# SerialPort.net
KiCad netlist of a schematic drawn in Altium Designer
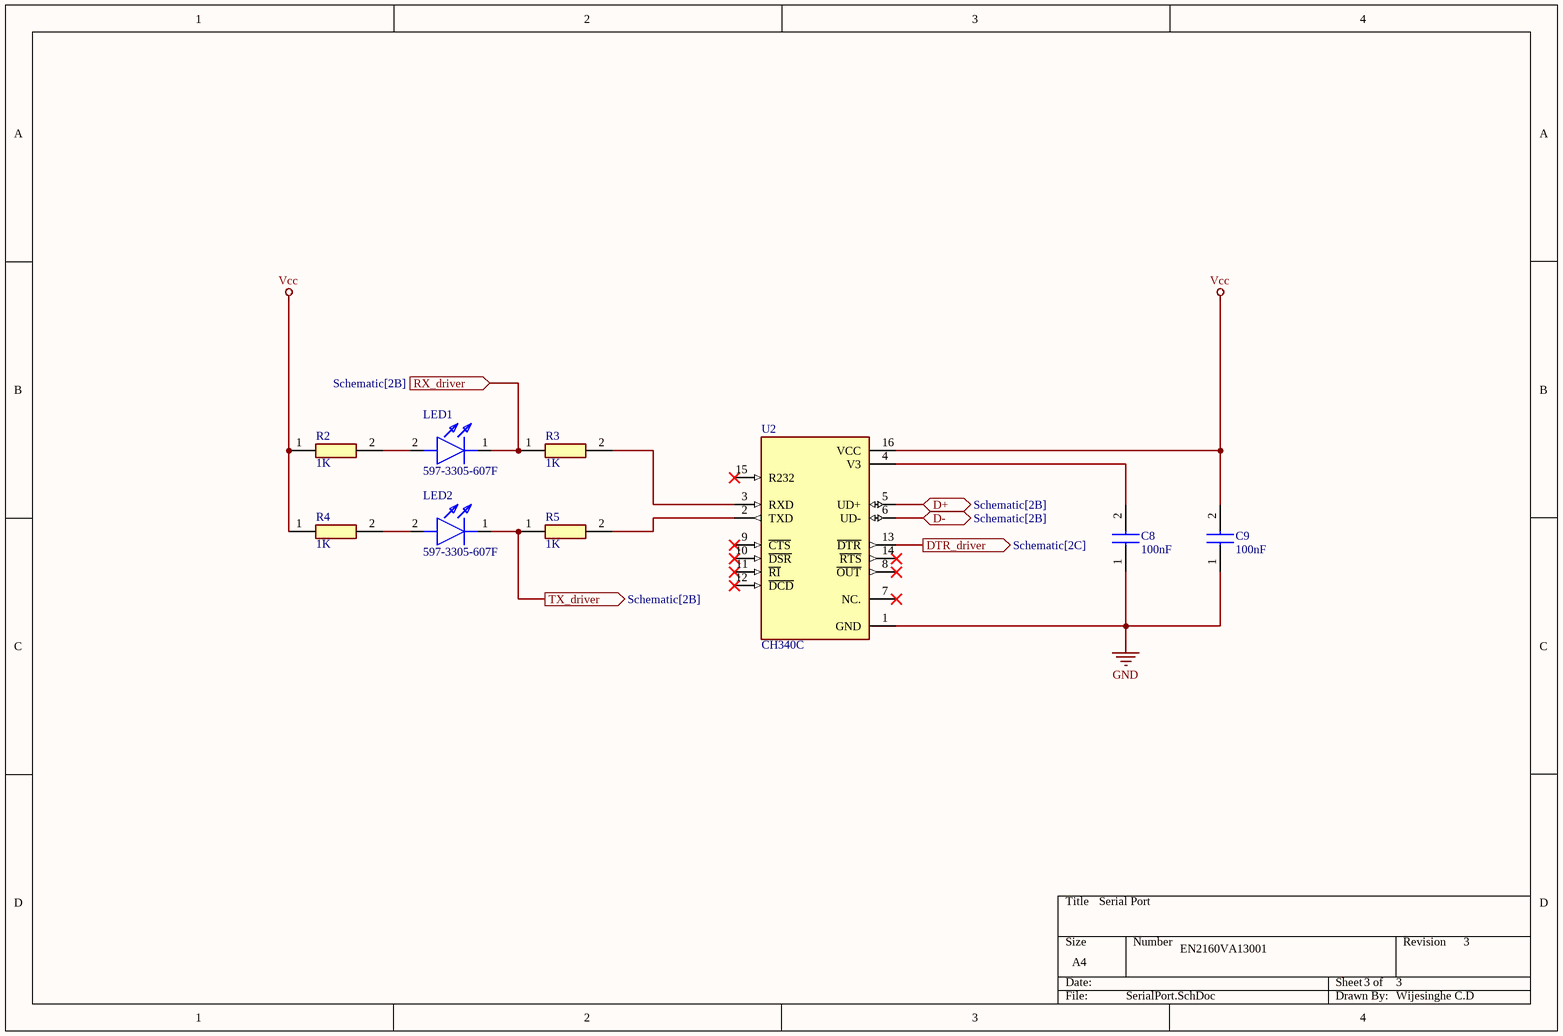
[diagram p0: SerialPort.SchDoc]

(export (version "E")
  (design (tool "Eeschema 10.0.6"))
  (components
    (comp (ref "C8")
      (value "100nF")
      (footprint "SamacSys:CAPC2013X137N")
      (description "Capacitor")
      (fields
        (field (name "MANUFACTURER_PART_NUMBER") "0805B104K500NT")
        (field (name "MOUSER PART NUMBER") "767-0805B104K500NT")
      )
      (libsource (lib "*") (part "0805B104K500NT"))
    )
    (comp (ref "C9")
      (value "100nF")
      (footprint "SamacSys:CAPC2013X137N")
      (description "Capacitor")
      (fields
        (field (name "MANUFACTURER_PART_NUMBER") "0805B104K500NT")
        (field (name "MOUSER PART NUMBER") "767-0805B104K500NT")
      )
      (libsource (lib "*") (part "0805B104K500NT"))
    )
    (comp (ref "LED1")
      (value "597-3305-607F")
      (footprint "SamacSys:LEDC2012X70N")
      (description "LED")
      (fields (field (name "MOUSER PART NUMBER") "645-597-3305-607F"))
      (libsource (lib "*") (part "597-3305-607F"))
    )
    (comp (ref "LED2")
      (value "597-3305-607F")
      (footprint "SamacSys:LEDC2012X70N")
      (description "LED")
      (fields (field (name "MOUSER PART NUMBER") "645-597-3305-607F"))
      (libsource (lib "*") (part "597-3305-607F"))
    )
    (comp (ref "R2")
      (value "1K")
      (footprint "SamacSys:RESC2012X60N")
      (description "Resistor")
      (fields
        (field (name "MANUFACTURER_PART_NUMBER") "RC0805FR-071KL")
        (field (name "MOUSER PART NUMBER") "603-RC0805FR-071KL")
      )
      (libsource (lib "*") (part "RC0805FR-071KL"))
    )
    (comp (ref "R3")
      (value "1K")
      (footprint "SamacSys:RESC2012X60N")
      (description "Resistor")
      (fields
        (field (name "MANUFACTURER_PART_NUMBER") "RC0805FR-071KL")
        (field (name "MOUSER PART NUMBER") "603-RC0805FR-071KL")
      )
      (libsource (lib "*") (part "RC0805FR-071KL"))
    )
    (comp (ref "R4")
      (value "1K")
      (footprint "SamacSys:RESC2012X60N")
      (description "Resistor")
      (fields
        (field (name "MANUFACTURER_PART_NUMBER") "RC0805FR-071KL")
        (field (name "MOUSER PART NUMBER") "603-RC0805FR-071KL")
      )
      (libsource (lib "*") (part "RC0805FR-071KL"))
    )
    (comp (ref "R5")
      (value "1K")
      (footprint "SamacSys:RESC2012X60N")
      (description "Resistor")
      (fields
        (field (name "MANUFACTURER_PART_NUMBER") "RC0805FR-071KL")
        (field (name "MOUSER PART NUMBER") "603-RC0805FR-071KL")
      )
      (libsource (lib "*") (part "RC0805FR-071KL"))
    )
    (comp (ref "U2")
      (value "CH340C")
      (footprint "SOIC127P600X180-16N")
      (description "USB to serial chip CH340")
      (fields (field (name "MF") "WCH"))
      (libsource (lib "CH340C_") (part "CH340C"))
    )
  )
  (nets
    (net (code "1") (name "/D+") (class "Default")
      (node (ref "U2") (pin "5") (pinfunction "UD+_5") (pintype "bidirectional"))
    )
    (net (code "2") (name "/D-") (class "Default")
      (node (ref "U2") (pin "6") (pinfunction "UD-_6") (pintype "bidirectional"))
    )
    (net (code "3") (name "/DTR_driver") (class "Default")
      (node (ref "U2") (pin "13") (pinfunction "~{DTR}_13") (pintype "output"))
    )
    (net (code "4") (name "/RX_driver") (class "Default")
      (node (ref "LED1") (pin "1") (pinfunction "K_1") (pintype "passive"))
      (node (ref "R3") (pin "1") (pinfunction "1_1") (pintype "passive"))
    )
    (net (code "5") (name "/TX_driver") (class "Default")
      (node (ref "LED2") (pin "1") (pinfunction "K_1") (pintype "passive"))
      (node (ref "R5") (pin "1") (pinfunction "1_1") (pintype "passive"))
    )
    (net (code "6") (name "GND") (class "Default")
      (node (ref "C8") (pin "1") (pinfunction "1_1") (pintype "passive"))
      (node (ref "C9") (pin "1") (pinfunction "1_1") (pintype "passive"))
      (node (ref "U2") (pin "1") (pinfunction "GND_1") (pintype "power_in"))
    )
    (net (code "7") (name "Net-(LED1-A)") (class "Default")
      (node (ref "LED1") (pin "2") (pinfunction "A_2") (pintype "passive"))
      (node (ref "R2") (pin "2") (pinfunction "2_2") (pintype "passive"))
    )
    (net (code "8") (name "Net-(LED2-A)") (class "Default")
      (node (ref "LED2") (pin "2") (pinfunction "A_2") (pintype "passive"))
      (node (ref "R4") (pin "2") (pinfunction "2_2") (pintype "passive"))
    )
    (net (code "9") (name "Net-(U2-RXD)") (class "Default")
      (node (ref "R3") (pin "2") (pinfunction "2_2") (pintype "passive"))
      (node (ref "U2") (pin "3") (pinfunction "RXD_3") (pintype "input"))
    )
    (net (code "10") (name "Net-(U2-TXD)") (class "Default")
      (node (ref "R5") (pin "2") (pinfunction "2_2") (pintype "passive"))
      (node (ref "U2") (pin "2") (pinfunction "TXD_2") (pintype "output"))
    )
    (net (code "11") (name "Net-(U2-V3)") (class "Default")
      (node (ref "C8") (pin "2") (pinfunction "2_2") (pintype "passive"))
      (node (ref "U2") (pin "4") (pinfunction "V3_4") (pintype "power_in"))
    )
    (net (code "12") (name "Vcc") (class "Default")
      (node (ref "C9") (pin "2") (pinfunction "2_2") (pintype "passive"))
      (node (ref "R2") (pin "1") (pinfunction "1_1") (pintype "passive"))
      (node (ref "R4") (pin "1") (pinfunction "1_1") (pintype "passive"))
      (node (ref "U2") (pin "16") (pinfunction "VCC_16") (pintype "power_in"))
    )
    (net (code "13") (name "unconnected-(U2-NC.-Pad7)") (class "Default")
      (node (ref "U2") (pin "7") (pinfunction "NC._7") (pintype "passive+no_connect"))
    )
    (net (code "14") (name "unconnected-(U2-R232-Pad15)") (class "Default")
      (node (ref "U2") (pin "15") (pinfunction "R232_15") (pintype "input+no_connect"))
    )
    (net (code "15") (name "unconnected-(U2-~{CTS}-Pad9)") (class "Default")
      (node (ref "U2") (pin "9") (pinfunction "~{CTS}_9") (pintype "input+no_connect"))
    )
    (net (code "16") (name "unconnected-(U2-~{DCD}-Pad12)") (class "Default")
      (node (ref "U2") (pin "12") (pinfunction "~{DCD}_12") (pintype "input+no_connect"))
    )
    (net (code "17") (name "unconnected-(U2-~{DSR}-Pad10)") (class "Default")
      (node (ref "U2") (pin "10") (pinfunction "~{DSR}_10") (pintype "input+no_connect"))
    )
    (net (code "18") (name "unconnected-(U2-~{OUT}-Pad8)") (class "Default")
      (node (ref "U2") (pin "8") (pinfunction "~{OUT}_8") (pintype "output+no_connect"))
    )
    (net (code "19") (name "unconnected-(U2-~{RI}-Pad11)") (class "Default")
      (node (ref "U2") (pin "11") (pinfunction "~{RI}_11") (pintype "input+no_connect"))
    )
    (net (code "20") (name "unconnected-(U2-~{RTS}-Pad14)") (class "Default")
      (node (ref "U2") (pin "14") (pinfunction "~{RTS}_14") (pintype "output+no_connect"))
    )
  )
)
